# Battery_Monitoring_V2.net
KiCad netlist of a schematic drawn in EAGLE
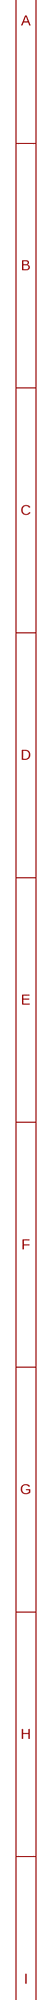
[diagram p0: schematic, sheet 1, part 1 of 2]
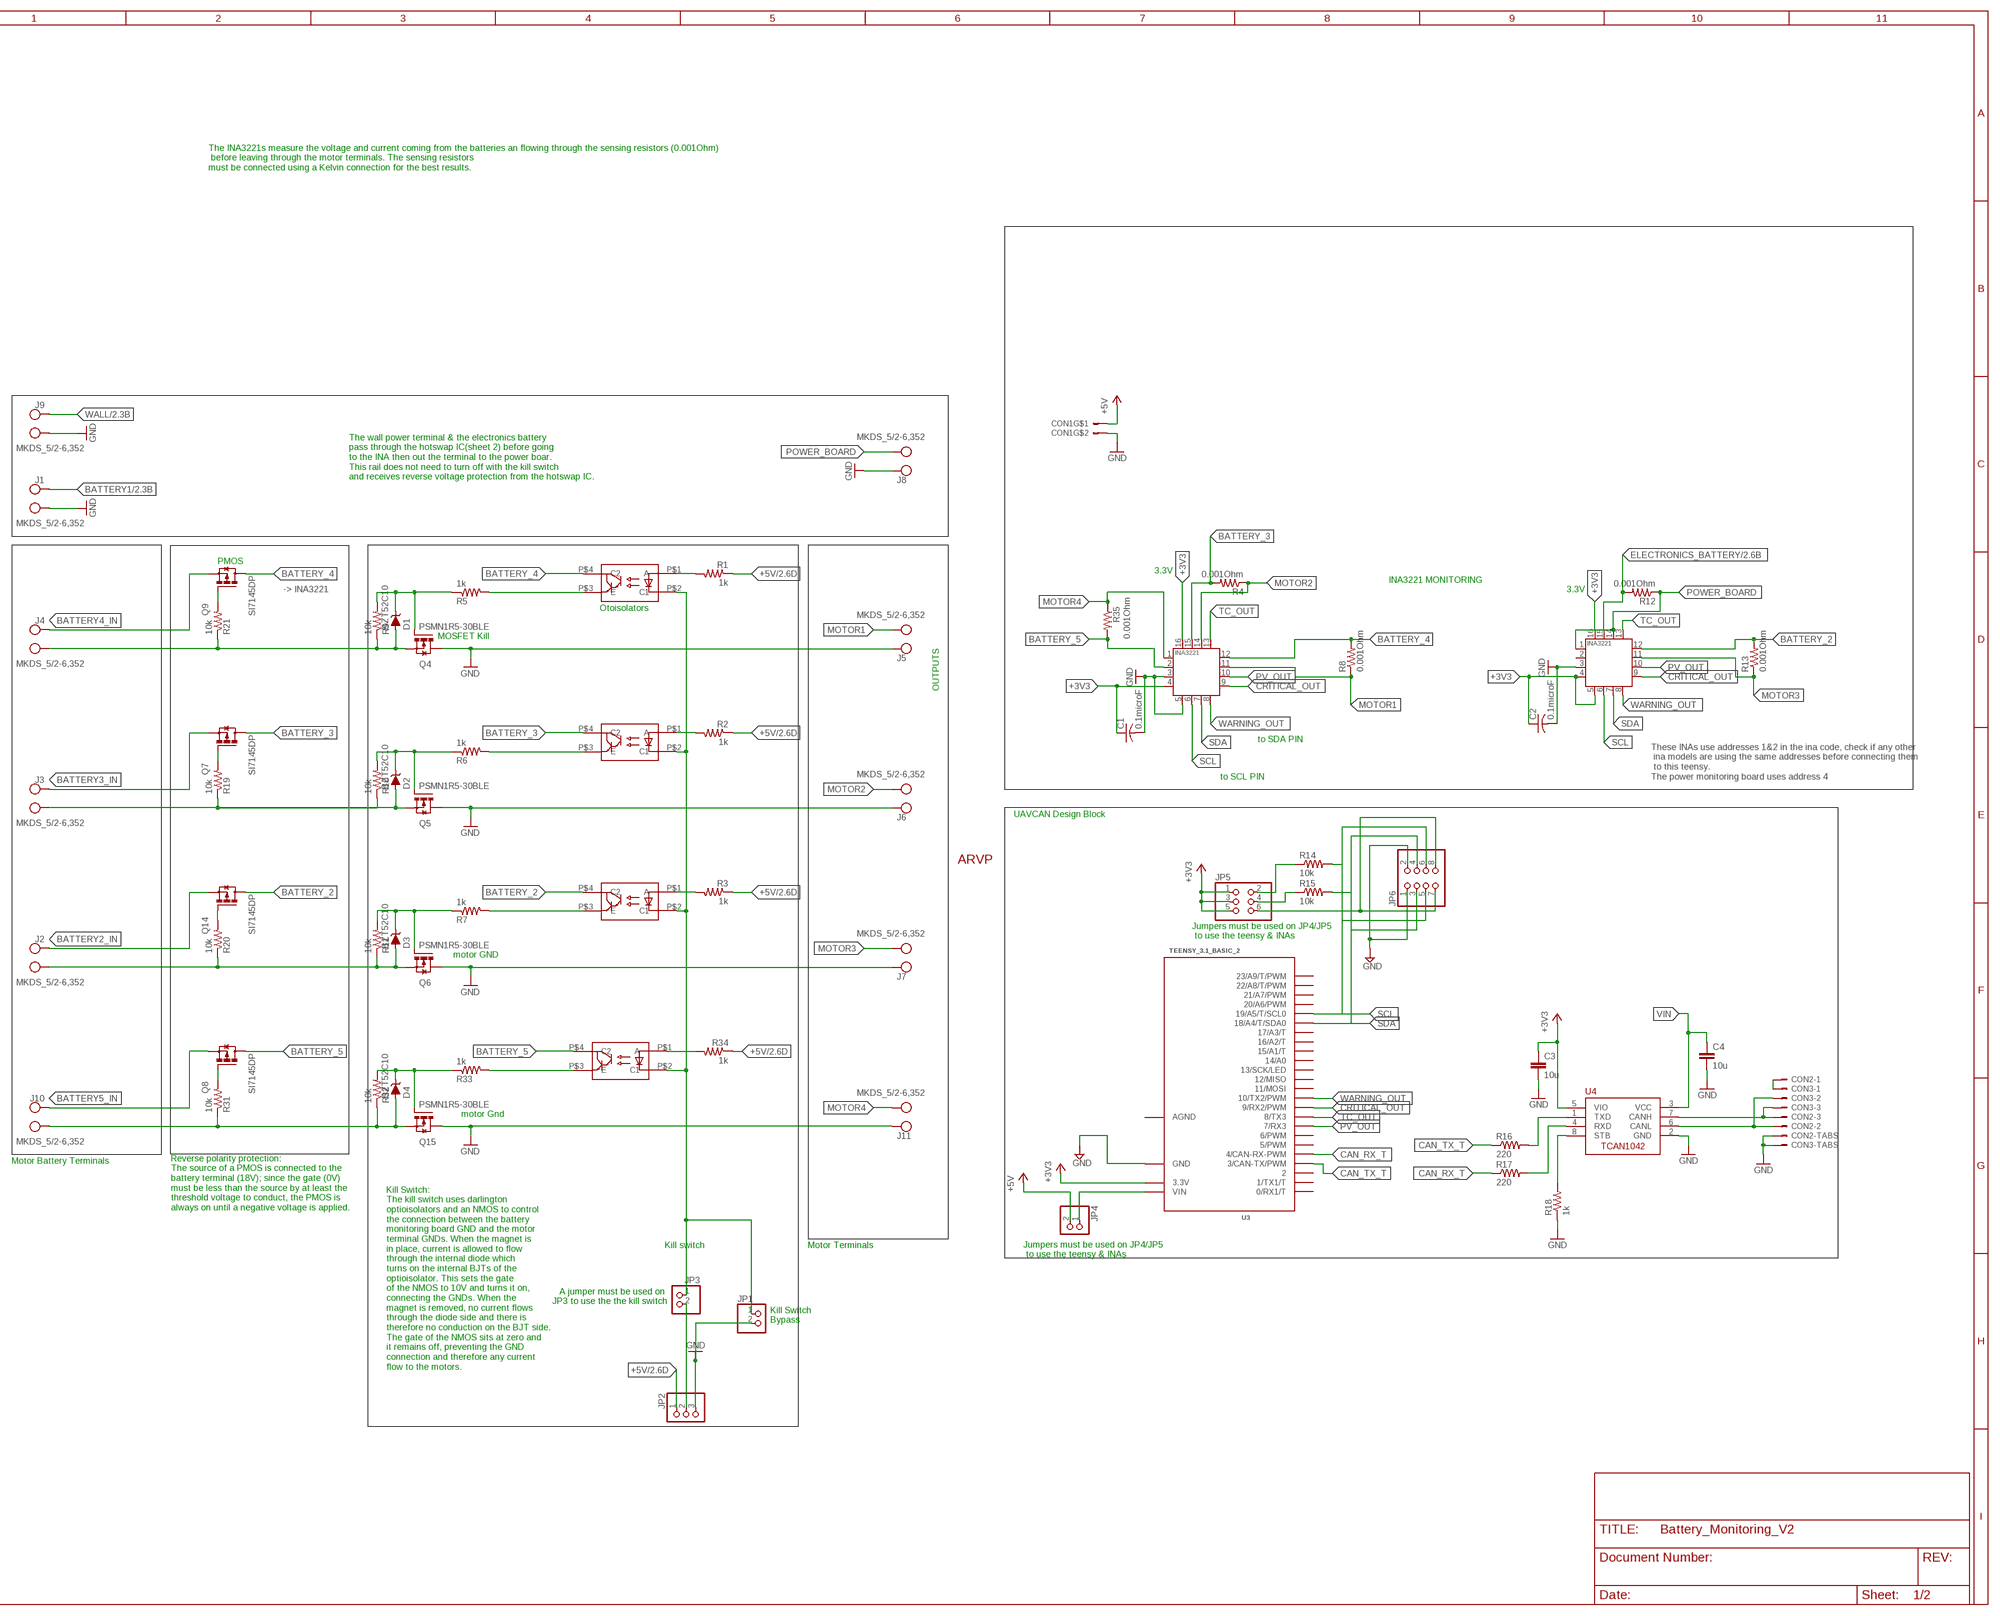
[diagram p1: schematic, sheet 1, part 2 of 2]
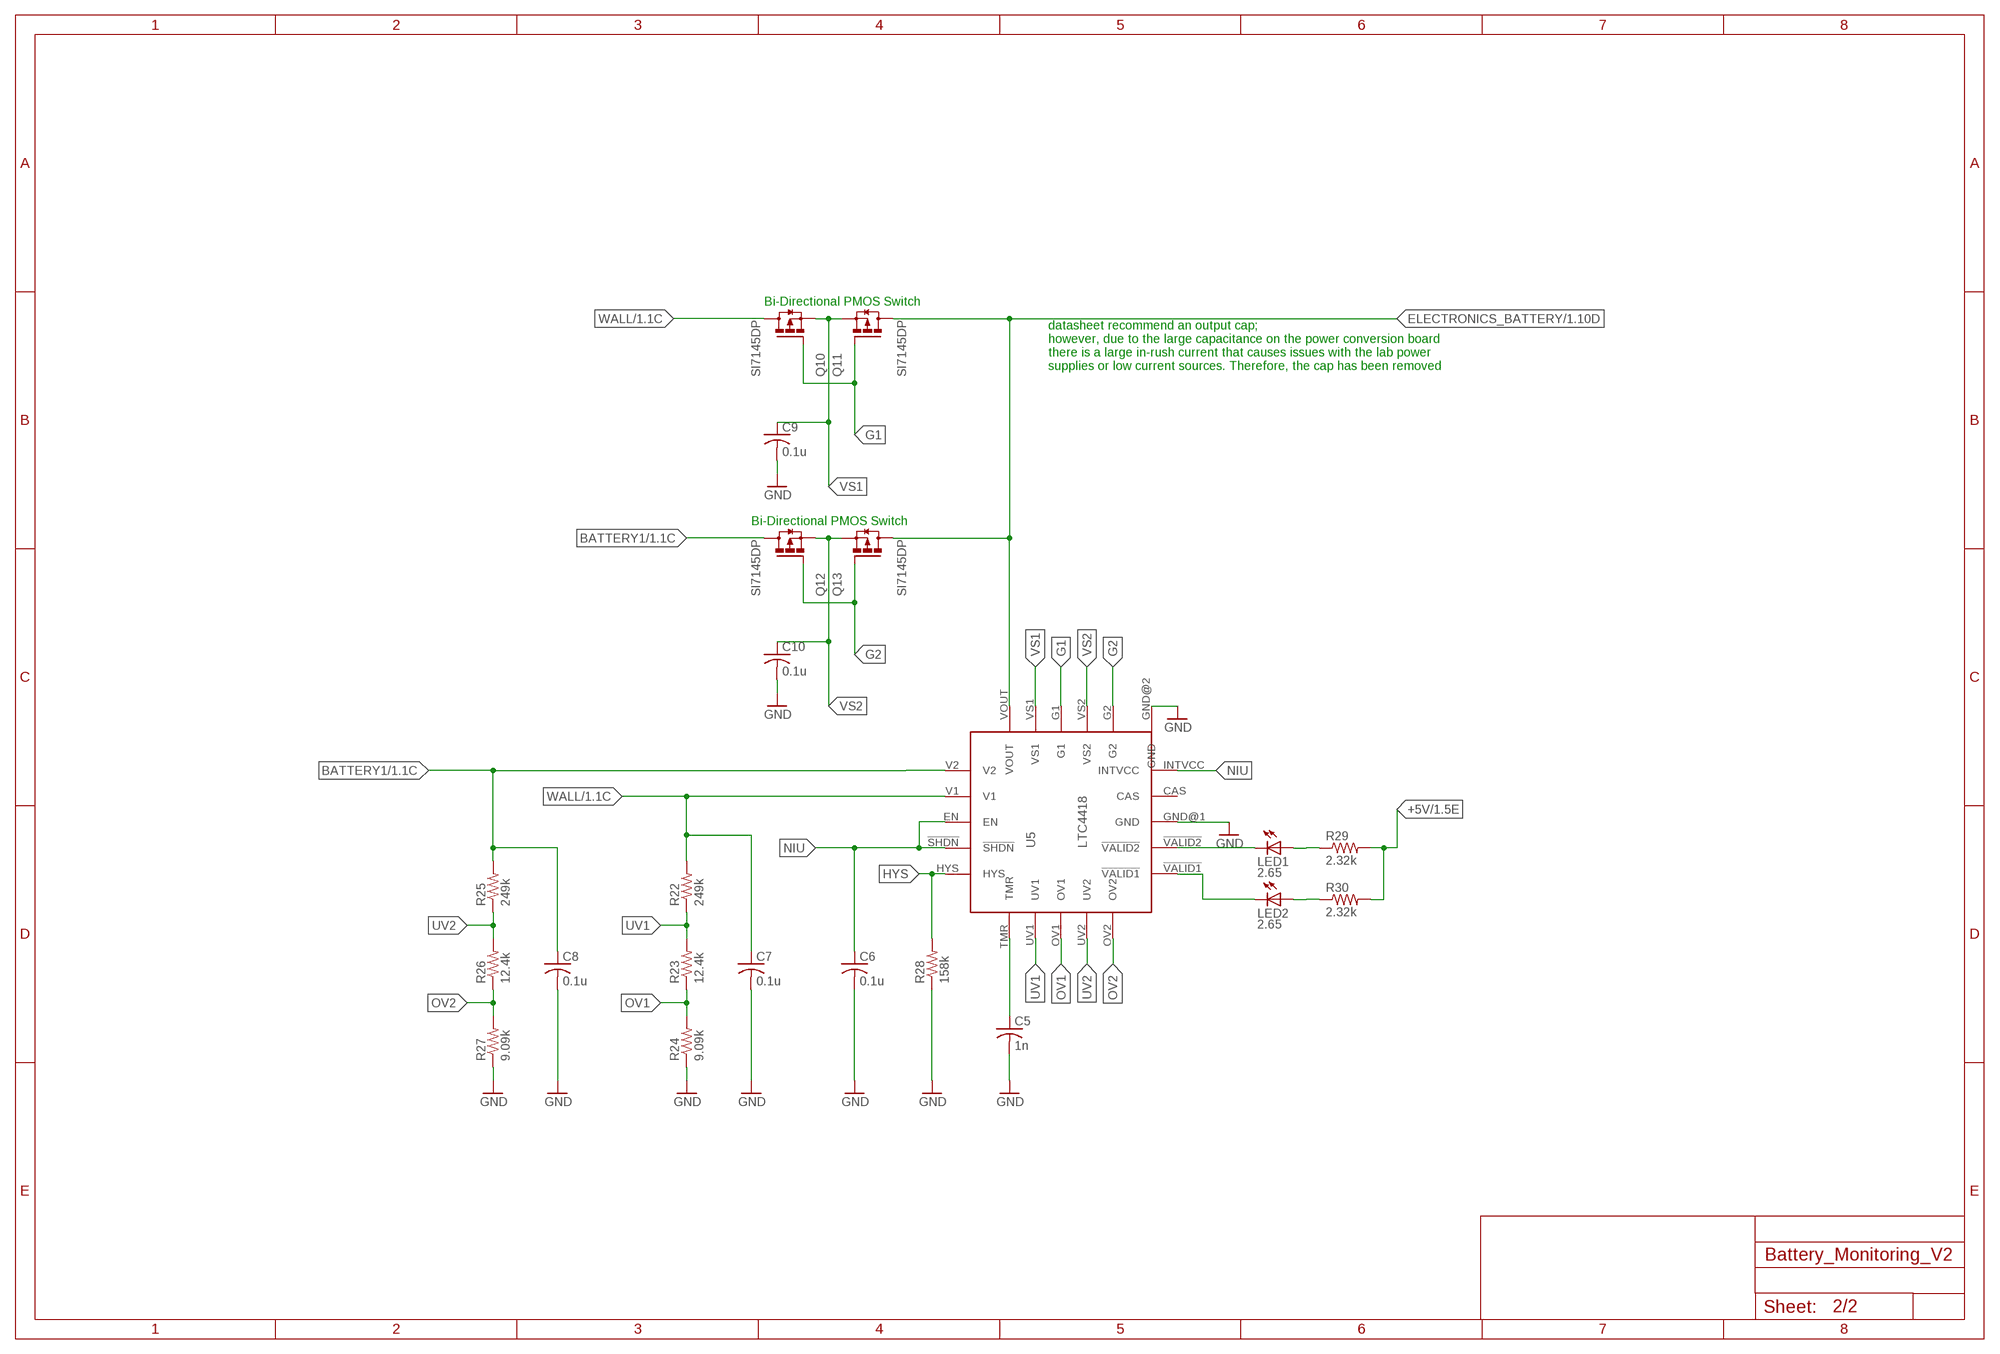
[diagram p2: schematic, sheet 2]

(export (version "E")
  (design (tool "Eeschema 10.0.6"))
  (components
    (comp (ref "ARVP1")
      (value "ARVP_LOGO")
      (footprint "eagle-import:ARVP")
      (libsource (lib "eagle-import") (part "ARVP_LOGO"))
    )
    (comp (ref "C1")
      (value "0.1microF")
      (footprint "eagle-import:C2012")
      (libsource (lib "eagle-import") (part "resistor_348_C-USC2012"))
    )
    (comp (ref "C2")
      (value "0.1microF")
      (footprint "eagle-import:C2012")
      (libsource (lib "eagle-import") (part "resistor_348_C-USC2012"))
    )
    (comp (ref "C3")
      (value "10u")
      (footprint "eagle-import:C0805")
      (libsource (lib "eagle-import") (part "C-EUC0805"))
    )
    (comp (ref "C4")
      (value "10u")
      (footprint "eagle-import:C0805")
      (libsource (lib "eagle-import") (part "C-EUC0805"))
    )
    (comp (ref "CON1")
      (value "MOLEX_5566-2")
      (footprint "eagle-import:5566-2")
      (libsource (lib "eagle-import") (part "MOLEX_5566-2"))
    )
    (comp (ref "CON2")
      (value "SM03B-GHS-TB")
      (footprint "eagle-import:SM03B-GHS-TB")
      (libsource (lib "eagle-import") (part "SM03B-GHS-TB"))
    )
    (comp (ref "CON3")
      (value "SM03B-GHS-TB")
      (footprint "eagle-import:SM03B-GHS-TB")
      (libsource (lib "eagle-import") (part "SM03B-GHS-TB"))
    )
    (comp (ref "D1")
      (value "BZT52C10")
      (footprint "eagle-import:SOD-123")
      (libsource (lib "eagle-import") (part "BZT52C10"))
    )
    (comp (ref "D2")
      (value "BZT52C10")
      (footprint "eagle-import:SOD-123")
      (libsource (lib "eagle-import") (part "BZT52C10"))
    )
    (comp (ref "D3")
      (value "BZT52C10")
      (footprint "eagle-import:SOD-123")
      (libsource (lib "eagle-import") (part "BZT52C10"))
    )
    (comp (ref "D4")
      (value "BZT52C10")
      (footprint "eagle-import:SOD-123")
      (libsource (lib "eagle-import") (part "BZT52C10"))
    )
    (comp (ref "J1")
      (value "MKDS_5/2-6,352")
      (footprint "eagle-import:MKDS_5_2-6,35")
      (libsource (lib "eagle-import") (part "MKDS_5/2-6,352"))
    )
    (comp (ref "J2")
      (value "MKDS_5/2-6,352")
      (footprint "eagle-import:MKDS_5_2-6,35")
      (libsource (lib "eagle-import") (part "MKDS_5/2-6,352"))
    )
    (comp (ref "J3")
      (value "MKDS_5/2-6,352")
      (footprint "eagle-import:MKDS_5_2-6,35")
      (libsource (lib "eagle-import") (part "MKDS_5/2-6,352"))
    )
    (comp (ref "J4")
      (value "MKDS_5/2-6,352")
      (footprint "eagle-import:MKDS_5_2-6,35")
      (libsource (lib "eagle-import") (part "MKDS_5/2-6,352"))
    )
    (comp (ref "J5")
      (value "MKDS_5/2-6,352")
      (footprint "eagle-import:MKDS_5_2-6,35")
      (libsource (lib "eagle-import") (part "MKDS_5/2-6,352"))
    )
    (comp (ref "J6")
      (value "MKDS_5/2-6,352")
      (footprint "eagle-import:MKDS_5_2-6,35")
      (libsource (lib "eagle-import") (part "MKDS_5/2-6,352"))
    )
    (comp (ref "J7")
      (value "MKDS_5/2-6,352")
      (footprint "eagle-import:MKDS_5_2-6,35")
      (libsource (lib "eagle-import") (part "MKDS_5/2-6,352"))
    )
    (comp (ref "J8")
      (value "MKDS_5/2-6,352")
      (footprint "eagle-import:MKDS_5_2-6,35")
      (libsource (lib "eagle-import") (part "MKDS_5/2-6,352"))
    )
    (comp (ref "J9")
      (value "MKDS_5/2-6,352")
      (footprint "eagle-import:MKDS_5_2-6,35")
      (libsource (lib "eagle-import") (part "MKDS_5/2-6,352"))
    )
    (comp (ref "J10")
      (value "MKDS_5/2-6,352")
      (footprint "eagle-import:MKDS_5_2-6,35")
      (libsource (lib "eagle-import") (part "MKDS_5/2-6,352"))
    )
    (comp (ref "J11")
      (value "MKDS_5/2-6,352")
      (footprint "eagle-import:MKDS_5_2-6,35")
      (libsource (lib "eagle-import") (part "MKDS_5/2-6,352"))
    )
    (comp (ref "JP1")
      (value "PINHD-1X2")
      (footprint "eagle-import:1X02")
      (libsource (lib "eagle-import") (part "PINHD-1X2"))
    )
    (comp (ref "JP2")
      (value "PINHD-1X3")
      (footprint "eagle-import:1X03")
      (libsource (lib "eagle-import") (part "PINHD-1X3"))
    )
    (comp (ref "JP3")
      (value "PINHD-1X2")
      (footprint "eagle-import:1X02")
      (libsource (lib "eagle-import") (part "PINHD-1X2"))
    )
    (comp (ref "JP4")
      (value "PINHD-1X2")
      (footprint "eagle-import:1X02")
      (libsource (lib "eagle-import") (part "PINHD-1X2"))
    )
    (comp (ref "JP5")
      (value "PINHD-2X3")
      (footprint "eagle-import:2X03")
      (libsource (lib "eagle-import") (part "PINHD-2X3"))
    )
    (comp (ref "JP6")
      (value "PINHD-2X4")
      (footprint "eagle-import:2X04")
      (libsource (lib "eagle-import") (part "PINHD-2X4"))
    )
    (comp (ref "Q1")
      (value "TCLD1000CT")
      (footprint "eagle-import:SOP-4L")
      (fields (field (name "SPICEPREFIX") "E"))
      (libsource (lib "eagle-import") (part "TCLD1000CT"))
    )
    (comp (ref "Q2")
      (value "TCLD1000CT")
      (footprint "eagle-import:SOP-4L")
      (libsource (lib "eagle-import") (part "TCLD1000CT"))
    )
    (comp (ref "Q3")
      (value "TCLD1000CT")
      (footprint "eagle-import:SOP-4L")
      (libsource (lib "eagle-import") (part "TCLD1000CT"))
    )
    (comp (ref "Q4")
      (value "PSMN1R5-30BLE")
      (footprint "eagle-import:SOT404_D2PAK")
      (libsource (lib "eagle-import") (part "PSMN1R5-30BLE"))
    )
    (comp (ref "Q5")
      (value "PSMN1R5-30BLE")
      (footprint "eagle-import:SOT404_D2PAK")
      (libsource (lib "eagle-import") (part "PSMN1R5-30BLE"))
    )
    (comp (ref "Q6")
      (value "PSMN1R5-30BLE")
      (footprint "eagle-import:SOT404_D2PAK")
      (libsource (lib "eagle-import") (part "PSMN1R5-30BLE"))
    )
    (comp (ref "Q7")
      (value "SI7145DP")
      (footprint "eagle-import:SO-8_PPAK_TEST")
      (fields (field (name "MPN") "SI7145DP-T1-GE3"))
      (libsource (lib "eagle-import") (part "Si7145DP_SI7145DP"))
    )
    (comp (ref "Q8")
      (value "SI7145DP")
      (footprint "eagle-import:SO-8_PPAK_TEST")
      (fields (field (name "MPN") "SI7145DP-T1-GE3"))
      (libsource (lib "eagle-import") (part "Si7145DP_SI7145DP"))
    )
    (comp (ref "Q9")
      (value "SI7145DP")
      (footprint "eagle-import:SO-8_PPAK_TEST")
      (fields (field (name "MPN") "SI7145DP-T1-GE3"))
      (libsource (lib "eagle-import") (part "Si7145DP_SI7145DP"))
    )
    (comp (ref "Q14")
      (value "SI7145DP")
      (footprint "eagle-import:SO-8_PPAK_TEST")
      (fields (field (name "MPN") "SI7145DP-T1-GE3"))
      (libsource (lib "eagle-import") (part "Si7145DP_SI7145DP"))
    )
    (comp (ref "Q15")
      (value "PSMN1R5-30BLE")
      (footprint "eagle-import:SOT404_D2PAK")
      (libsource (lib "eagle-import") (part "PSMN1R5-30BLE"))
    )
    (comp (ref "Q16")
      (value "TCLD1000CT")
      (footprint "eagle-import:SOP-4L")
      (libsource (lib "eagle-import") (part "TCLD1000CT"))
    )
    (comp (ref "R1")
      (value "1k")
      (footprint "eagle-import:R0805")
      (libsource (lib "eagle-import") (part "adafruit_420_R-US_R0805"))
    )
    (comp (ref "R2")
      (value "1k")
      (footprint "eagle-import:R0805")
      (libsource (lib "eagle-import") (part "adafruit_420_R-US_R0805"))
    )
    (comp (ref "R3")
      (value "1k")
      (footprint "eagle-import:R0805")
      (libsource (lib "eagle-import") (part "adafruit_420_R-US_R0805"))
    )
    (comp (ref "R4")
      (value "0.001Ohm")
      (footprint "eagle-import:3920")
      (libsource (lib "eagle-import") (part "HCS3920FT1L00"))
    )
    (comp (ref "R5")
      (value "1k")
      (footprint "eagle-import:M1206")
      (libsource (lib "eagle-import") (part "adafruit_420_R-US_M1206"))
    )
    (comp (ref "R6")
      (value "1k")
      (footprint "eagle-import:M1206")
      (libsource (lib "eagle-import") (part "adafruit_420_R-US_M1206"))
    )
    (comp (ref "R7")
      (value "1k")
      (footprint "eagle-import:M1206")
      (libsource (lib "eagle-import") (part "adafruit_420_R-US_M1206"))
    )
    (comp (ref "R8")
      (value "0.001Ohm")
      (footprint "eagle-import:3920")
      (libsource (lib "eagle-import") (part "HCS3920FT1L00"))
    )
    (comp (ref "R9")
      (value "10k")
      (footprint "eagle-import:M1206")
      (libsource (lib "eagle-import") (part "adafruit_420_R-US_M1206"))
    )
    (comp (ref "R10")
      (value "10k")
      (footprint "eagle-import:M1206")
      (libsource (lib "eagle-import") (part "adafruit_420_R-US_M1206"))
    )
    (comp (ref "R11")
      (value "10k")
      (footprint "eagle-import:M1206")
      (libsource (lib "eagle-import") (part "adafruit_420_R-US_M1206"))
    )
    (comp (ref "R12")
      (value "0.001Ohm")
      (footprint "eagle-import:3920")
      (libsource (lib "eagle-import") (part "HCS3920FT1L00"))
    )
    (comp (ref "R13")
      (value "0.001Ohm")
      (footprint "eagle-import:3920")
      (libsource (lib "eagle-import") (part "HCS3920FT1L00"))
    )
    (comp (ref "R14")
      (value "10k")
      (footprint "eagle-import:R1206")
      (libsource (lib "eagle-import") (part "rcl_334_R-US_R1206"))
    )
    (comp (ref "R15")
      (value "10k")
      (footprint "eagle-import:R1206")
      (libsource (lib "eagle-import") (part "rcl_334_R-US_R1206"))
    )
    (comp (ref "R16")
      (value "220")
      (footprint "eagle-import:R0805")
      (libsource (lib "eagle-import") (part "rcl_334_R-US_R0805"))
    )
    (comp (ref "R17")
      (value "220")
      (footprint "eagle-import:R0805")
      (libsource (lib "eagle-import") (part "rcl_334_R-US_R0805"))
    )
    (comp (ref "R18")
      (value "1k")
      (footprint "eagle-import:R0805")
      (libsource (lib "eagle-import") (part "rcl_334_R-US_R0805"))
    )
    (comp (ref "R19")
      (value "10k")
      (footprint "eagle-import:M1206")
      (fields (field (name "MPN") "RC0603FR-0710KL"))
      (libsource (lib "eagle-import") (part "R-US_M1206"))
    )
    (comp (ref "R20")
      (value "10k")
      (footprint "eagle-import:M1206")
      (fields (field (name "MPN") "RC0603FR-0710KL"))
      (libsource (lib "eagle-import") (part "R-US_M1206"))
    )
    (comp (ref "R21")
      (value "10k")
      (footprint "eagle-import:M1206")
      (fields (field (name "MPN") "RC0603FR-0710KL"))
      (libsource (lib "eagle-import") (part "adafruit_420_R-US_M1206"))
    )
    (comp (ref "R31")
      (value "10k")
      (footprint "eagle-import:M1206")
      (fields (field (name "MPN") "RC0603FR-0710KL"))
      (libsource (lib "eagle-import") (part "R-US_M1206"))
    )
    (comp (ref "R32")
      (value "10k")
      (footprint "eagle-import:M1206")
      (libsource (lib "eagle-import") (part "adafruit_420_R-US_M1206"))
    )
    (comp (ref "R33")
      (value "1k")
      (footprint "eagle-import:M1206")
      (libsource (lib "eagle-import") (part "adafruit_420_R-US_M1206"))
    )
    (comp (ref "R34")
      (value "1k")
      (footprint "eagle-import:R0805")
      (libsource (lib "eagle-import") (part "adafruit_420_R-US_R0805"))
    )
    (comp (ref "R35")
      (value "0.001Ohm")
      (footprint "eagle-import:3920")
      (libsource (lib "eagle-import") (part "HCS3920FT1L00"))
    )
    (comp (ref "U1")
      (value "INA3221.")
      (footprint "eagle-import:HVQFN16_4X4")
      (libsource (lib "eagle-import") (part "INA3221."))
    )
    (comp (ref "U2")
      (value "INA3221.")
      (footprint "eagle-import:HVQFN16_4X4")
      (libsource (lib "eagle-import") (part "INA3221."))
    )
    (comp (ref "U3")
      (value "TEENSY_3.1_BASIC_2")
      (footprint "eagle-import:TEENSY_3.1_BASIC_2")
      (libsource (lib "eagle-import") (part "TEENSY_3.1_BASIC_2"))
    )
    (comp (ref "U4")
      (value "TCAN1042HVDR")
      (footprint "eagle-import:SO-8")
      (libsource (lib "eagle-import") (part "TCAN1042HVDR"))
    )
    (comp (ref "C5")
      (value "1n")
      (footprint "eagle-import:C0805")
      (libsource (lib "eagle-import") (part "C-USC0805"))
    )
    (comp (ref "C6")
      (value "0.1u")
      (footprint "eagle-import:C0805")
      (libsource (lib "eagle-import") (part "C-USC0805"))
    )
    (comp (ref "C7")
      (value "0.1u")
      (footprint "eagle-import:C0805")
      (libsource (lib "eagle-import") (part "C-USC0805"))
    )
    (comp (ref "C8")
      (value "0.1u")
      (footprint "eagle-import:C0805")
      (libsource (lib "eagle-import") (part "C-USC0805"))
    )
    (comp (ref "C9")
      (value "0.1u")
      (footprint "eagle-import:C0805")
      (libsource (lib "eagle-import") (part "C-USC0805"))
    )
    (comp (ref "C10")
      (value "0.1u")
      (footprint "eagle-import:C0805")
      (libsource (lib "eagle-import") (part "C-USC0805"))
    )
    (comp (ref "LED1")
      (value "2.65")
      (footprint "eagle-import:SML0805")
      (libsource (lib "eagle-import") (part "LEDSML0805"))
    )
    (comp (ref "LED2")
      (value "2.65")
      (footprint "eagle-import:SML0805")
      (libsource (lib "eagle-import") (part "LEDSML0805"))
    )
    (comp (ref "Q10")
      (value "SI7145DP")
      (footprint "eagle-import:SO-8_PPAK_TEST")
      (libsource (lib "eagle-import") (part "SI7145DP"))
    )
    (comp (ref "Q11")
      (value "SI7145DP")
      (footprint "eagle-import:SO-8_PPAK_TEST")
      (libsource (lib "eagle-import") (part "SI7145DP"))
    )
    (comp (ref "Q12")
      (value "SI7145DP")
      (footprint "eagle-import:SO-8_PPAK_TEST")
      (libsource (lib "eagle-import") (part "SI7145DP"))
    )
    (comp (ref "Q13")
      (value "SI7145DP")
      (footprint "eagle-import:SO-8_PPAK_TEST")
      (libsource (lib "eagle-import") (part "SI7145DP"))
    )
    (comp (ref "R22")
      (value "249k")
      (footprint "eagle-import:R1206")
      (libsource (lib "eagle-import") (part "adafruit_420_R-US_R1206"))
    )
    (comp (ref "R23")
      (value "12.4k")
      (footprint "eagle-import:R0805")
      (libsource (lib "eagle-import") (part "adafruit_420_R-US_R0805"))
    )
    (comp (ref "R24")
      (value "9.09k")
      (footprint "eagle-import:R0805")
      (libsource (lib "eagle-import") (part "adafruit_420_R-US_R0805"))
    )
    (comp (ref "R25")
      (value "249k")
      (footprint "eagle-import:R1206")
      (libsource (lib "eagle-import") (part "adafruit_420_R-US_R1206"))
    )
    (comp (ref "R26")
      (value "12.4k")
      (footprint "eagle-import:R0805")
      (libsource (lib "eagle-import") (part "adafruit_420_R-US_R0805"))
    )
    (comp (ref "R27")
      (value "9.09k")
      (footprint "eagle-import:R0805")
      (libsource (lib "eagle-import") (part "adafruit_420_R-US_R0805"))
    )
    (comp (ref "R28")
      (value "158k")
      (footprint "eagle-import:R0805")
      (libsource (lib "eagle-import") (part "adafruit_420_R-US_R0805"))
    )
    (comp (ref "R29")
      (value "2.32k")
      (footprint "eagle-import:R0805")
      (libsource (lib "eagle-import") (part "adafruit_420_R-US_R0805"))
    )
    (comp (ref "R30")
      (value "2.32k")
      (footprint "eagle-import:R0805")
      (libsource (lib "eagle-import") (part "adafruit_420_R-US_R0805"))
    )
    (comp (ref "U5")
      (value "LTC4418")
      (footprint "eagle-import:20-QFN(4X4)")
      (libsource (lib "eagle-import") (part "LTC4418"))
    )
  )
  (nets
    (net (code "1") (name "+3V3") (class "Default")
      (node (ref "C1") (pin "1") (pinfunction "1_1") (pintype "passive"))
      (node (ref "C2") (pin "1") (pinfunction "1_1") (pintype "passive"))
      (node (ref "C3") (pin "1") (pinfunction "1_1") (pintype "passive"))
      (node (ref "JP5") (pin "1") (pinfunction "1_1") (pintype "passive"))
      (node (ref "JP5") (pin "3") (pinfunction "3_3") (pintype "passive"))
      (node (ref "JP5") (pin "5") (pinfunction "5_5") (pintype "passive"))
      (node (ref "U1") (pin "16") (pinfunction "VPU_16") (pintype "input"))
      (node (ref "U1") (pin "4") (pinfunction "VS_4") (pintype "power_in"))
      (node (ref "U2") (pin "16") (pinfunction "VPU_16") (pintype "input"))
      (node (ref "U2") (pin "4") (pinfunction "VS_4") (pintype "power_in"))
      (node (ref "U2") (pin "5") (pinfunction "A0_5") (pintype "input"))
      (node (ref "U3") (pin "3.3V") (pinfunction "3.3V_3.3V") (pintype "power_in"))
      (node (ref "U4") (pin "5") (pinfunction "VIO_5") (pintype "bidirectional"))
    )
    (net (code "2") (name "+5V") (class "Default")
      (node (ref "CON1") (pin "1") (pinfunction "S_1") (pintype "passive"))
      (node (ref "JP2") (pin "1") (pinfunction "1_1") (pintype "passive"))
      (node (ref "JP4") (pin "2") (pinfunction "2_2") (pintype "passive"))
      (node (ref "R1") (pin "1") (pinfunction "1_1") (pintype "passive"))
      (node (ref "R2") (pin "1") (pinfunction "1_1") (pintype "passive"))
      (node (ref "R29") (pin "2") (pinfunction "2_2") (pintype "passive"))
      (node (ref "R3") (pin "1") (pinfunction "1_1") (pintype "passive"))
      (node (ref "R30") (pin "2") (pinfunction "2_2") (pintype "passive"))
    )
    (net (code "3") (name "+5V{slash}2.6D") (class "Default")
      (node (ref "R34") (pin "1") (pinfunction "1_1") (pintype "passive"))
    )
    (net (code "4") (name "AGND") (class "Default")
      (node (ref "U3") (pin "AGND") (pinfunction "AGND_AGND") (pintype "power_in"))
    )
    (net (code "5") (name "BATTERY1") (class "Default")
      (node (ref "C8") (pin "1") (pinfunction "1_1") (pintype "passive"))
      (node (ref "J1") (pin "2") (pinfunction "KL1_2") (pintype "passive"))
      (node (ref "Q12") (pin "D@1") (pinfunction "D_D@1") (pintype "passive"))
      (node (ref "Q12") (pin "D@2") (pinfunction "D_D@2") (pintype "passive"))
      (node (ref "Q12") (pin "D@3") (pinfunction "D_D@3") (pintype "passive"))
      (node (ref "Q12") (pin "D@4") (pinfunction "D_D@4") (pintype "passive"))
      (node (ref "Q12") (pin "D@5") (pinfunction "D_D@5") (pintype "passive"))
      (node (ref "R25") (pin "2") (pinfunction "2_2") (pintype "passive"))
      (node (ref "U5") (pin "V2") (pinfunction "V2_V2") (pintype "bidirectional"))
    )
    (net (code "6") (name "BATTERY2_IN") (class "Default")
      (node (ref "J2") (pin "2") (pinfunction "KL1_2") (pintype "passive"))
      (node (ref "Q14") (pin "S@1") (pinfunction "S_S@1") (pintype "passive"))
      (node (ref "Q14") (pin "S@2") (pinfunction "S_S@2") (pintype "passive"))
      (node (ref "Q14") (pin "S@3") (pinfunction "S_S@3") (pintype "passive"))
    )
    (net (code "7") (name "BATTERY3_IN") (class "Default")
      (node (ref "J3") (pin "2") (pinfunction "KL1_2") (pintype "passive"))
      (node (ref "Q7") (pin "S@1") (pinfunction "S_S@1") (pintype "passive"))
      (node (ref "Q7") (pin "S@2") (pinfunction "S_S@2") (pintype "passive"))
      (node (ref "Q7") (pin "S@3") (pinfunction "S_S@3") (pintype "passive"))
    )
    (net (code "8") (name "BATTERY4_IN") (class "Default")
      (node (ref "J4") (pin "2") (pinfunction "KL1_2") (pintype "passive"))
      (node (ref "Q9") (pin "S@1") (pinfunction "S_S@1") (pintype "passive"))
      (node (ref "Q9") (pin "S@2") (pinfunction "S_S@2") (pintype "passive"))
      (node (ref "Q9") (pin "S@3") (pinfunction "S_S@3") (pintype "passive"))
    )
    (net (code "9") (name "BATTERY5_IN") (class "Default")
      (node (ref "J10") (pin "2") (pinfunction "KL1_2") (pintype "passive"))
      (node (ref "Q8") (pin "S@1") (pinfunction "S_S@1") (pintype "passive"))
      (node (ref "Q8") (pin "S@2") (pinfunction "S_S@2") (pintype "passive"))
      (node (ref "Q8") (pin "S@3") (pinfunction "S_S@3") (pintype "passive"))
    )
    (net (code "10") (name "BATTERY_2") (class "Default")
      (node (ref "Q14") (pin "D@1") (pinfunction "D_D@1") (pintype "passive"))
      (node (ref "Q14") (pin "D@2") (pinfunction "D_D@2") (pintype "passive"))
      (node (ref "Q14") (pin "D@3") (pinfunction "D_D@3") (pintype "passive"))
      (node (ref "Q14") (pin "D@4") (pinfunction "D_D@4") (pintype "passive"))
      (node (ref "Q14") (pin "D@5") (pinfunction "D_D@5") (pintype "passive"))
      (node (ref "Q3") (pin "P$4") (pinfunction "C2_P$4") (pintype "bidirectional"))
      (node (ref "R13") (pin "P$2") (pinfunction "2_P$2") (pintype "passive"))
      (node (ref "U2") (pin "12") (pinfunction "IN+1_12") (pintype "input"))
    )
    (net (code "11") (name "BATTERY_3") (class "Default")
      (node (ref "Q2") (pin "P$4") (pinfunction "C2_P$4") (pintype "bidirectional"))
      (node (ref "Q7") (pin "D@1") (pinfunction "D_D@1") (pintype "passive"))
      (node (ref "Q7") (pin "D@2") (pinfunction "D_D@2") (pintype "passive"))
      (node (ref "Q7") (pin "D@3") (pinfunction "D_D@3") (pintype "passive"))
      (node (ref "Q7") (pin "D@4") (pinfunction "D_D@4") (pintype "passive"))
      (node (ref "Q7") (pin "D@5") (pinfunction "D_D@5") (pintype "passive"))
      (node (ref "R4") (pin "P$2") (pinfunction "2_P$2") (pintype "passive"))
      (node (ref "U1") (pin "15") (pinfunction "IN+2_15") (pintype "input"))
    )
    (net (code "12") (name "BATTERY_4") (class "Default")
      (node (ref "Q1") (pin "P$4") (pinfunction "C2_P$4") (pintype "bidirectional"))
      (node (ref "Q9") (pin "D@1") (pinfunction "D_D@1") (pintype "passive"))
      (node (ref "Q9") (pin "D@2") (pinfunction "D_D@2") (pintype "passive"))
      (node (ref "Q9") (pin "D@3") (pinfunction "D_D@3") (pintype "passive"))
      (node (ref "Q9") (pin "D@4") (pinfunction "D_D@4") (pintype "passive"))
      (node (ref "Q9") (pin "D@5") (pinfunction "D_D@5") (pintype "passive"))
      (node (ref "R8") (pin "P$2") (pinfunction "2_P$2") (pintype "passive"))
      (node (ref "U1") (pin "12") (pinfunction "IN+1_12") (pintype "input"))
    )
    (net (code "13") (name "BATTERY_5") (class "Default")
      (node (ref "Q16") (pin "P$4") (pinfunction "C2_P$4") (pintype "bidirectional"))
      (node (ref "Q8") (pin "D@1") (pinfunction "D_D@1") (pintype "passive"))
      (node (ref "Q8") (pin "D@2") (pinfunction "D_D@2") (pintype "passive"))
      (node (ref "Q8") (pin "D@3") (pinfunction "D_D@3") (pintype "passive"))
      (node (ref "Q8") (pin "D@4") (pinfunction "D_D@4") (pintype "passive"))
      (node (ref "Q8") (pin "D@5") (pinfunction "D_D@5") (pintype "passive"))
      (node (ref "R35") (pin "P$2") (pinfunction "2_P$2") (pintype "passive"))
      (node (ref "U1") (pin "2") (pinfunction "IN+3_2") (pintype "input"))
    )
    (net (code "14") (name "CAN_RX_T") (class "Default")
      (node (ref "R17") (pin "1") (pinfunction "1_1") (pintype "passive"))
      (node (ref "U3") (pin "4") (pinfunction "4/CAN-RX-PWM_4") (pintype "bidirectional"))
    )
    (net (code "15") (name "CAN_TX_T") (class "Default")
      (node (ref "R16") (pin "1") (pinfunction "1_1") (pintype "passive"))
      (node (ref "U3") (pin "3") (pinfunction "3/CAN-TX/PWM_3") (pintype "bidirectional"))
    )
    (net (code "16") (name "CRITICAL_OUT") (class "Default")
      (node (ref "U1") (pin "9") (pinfunction "CRITICAL_9") (pintype "output"))
      (node (ref "U2") (pin "9") (pinfunction "CRITICAL_9") (pintype "output"))
      (node (ref "U3") (pin "9") (pinfunction "9/RX2/PWM_9") (pintype "bidirectional"))
    )
    (net (code "17") (name "ELECTRONICS_BATTERY") (class "Default")
      (node (ref "Q11") (pin "D@1") (pinfunction "D_D@1") (pintype "passive"))
      (node (ref "Q11") (pin "D@2") (pinfunction "D_D@2") (pintype "passive"))
      (node (ref "Q11") (pin "D@3") (pinfunction "D_D@3") (pintype "passive"))
      (node (ref "Q11") (pin "D@4") (pinfunction "D_D@4") (pintype "passive"))
      (node (ref "Q11") (pin "D@5") (pinfunction "D_D@5") (pintype "passive"))
      (node (ref "Q13") (pin "D@1") (pinfunction "D_D@1") (pintype "passive"))
      (node (ref "Q13") (pin "D@2") (pinfunction "D_D@2") (pintype "passive"))
      (node (ref "Q13") (pin "D@3") (pinfunction "D_D@3") (pintype "passive"))
      (node (ref "Q13") (pin "D@4") (pinfunction "D_D@4") (pintype "passive"))
      (node (ref "Q13") (pin "D@5") (pinfunction "D_D@5") (pintype "passive"))
      (node (ref "R12") (pin "P$2") (pinfunction "2_P$2") (pintype "passive"))
      (node (ref "U2") (pin "15") (pinfunction "IN+2_15") (pintype "input"))
      (node (ref "U5") (pin "VOUT") (pinfunction "VOUT_VOUT") (pintype "power_in"))
    )
    (net (code "18") (name "G1") (class "Default")
      (node (ref "Q10") (pin "G") (pinfunction "G_G") (pintype "passive"))
      (node (ref "Q11") (pin "G") (pinfunction "G_G") (pintype "passive"))
      (node (ref "U5") (pin "G1") (pinfunction "G1_G1") (pintype "bidirectional"))
    )
    (net (code "19") (name "G2") (class "Default")
      (node (ref "Q12") (pin "G") (pinfunction "G_G") (pintype "passive"))
      (node (ref "Q13") (pin "G") (pinfunction "G_G") (pintype "passive"))
      (node (ref "U5") (pin "G2") (pinfunction "G2_G2") (pintype "bidirectional"))
    )
    (net (code "20") (name "GND") (class "Default")
      (node (ref "C1") (pin "2") (pinfunction "2_2") (pintype "passive"))
      (node (ref "C10") (pin "2") (pinfunction "2_2") (pintype "passive"))
      (node (ref "C2") (pin "2") (pinfunction "2_2") (pintype "passive"))
      (node (ref "C3") (pin "2") (pinfunction "2_2") (pintype "passive"))
      (node (ref "C4") (pin "2") (pinfunction "2_2") (pintype "passive"))
      (node (ref "C5") (pin "2") (pinfunction "2_2") (pintype "passive"))
      (node (ref "C6") (pin "2") (pinfunction "2_2") (pintype "passive"))
      (node (ref "C7") (pin "2") (pinfunction "2_2") (pintype "passive"))
      (node (ref "C8") (pin "2") (pinfunction "2_2") (pintype "passive"))
      (node (ref "C9") (pin "2") (pinfunction "2_2") (pintype "passive"))
      (node (ref "CON1") (pin "2") (pinfunction "S_2") (pintype "passive"))
      (node (ref "CON2") (pin "P$4") (pinfunction "S_P$4") (pintype "passive"))
      (node (ref "CON2") (pin "P$5") (pinfunction "S_P$5") (pintype "passive"))
      (node (ref "CON3") (pin "P$4") (pinfunction "S_P$4") (pintype "passive"))
      (node (ref "CON3") (pin "P$5") (pinfunction "S_P$5") (pintype "passive"))
      (node (ref "J1") (pin "1") (pinfunction "KL_1") (pintype "passive"))
      (node (ref "J11") (pin "2") (pinfunction "KL1_2") (pintype "passive"))
      (node (ref "J5") (pin "2") (pinfunction "KL1_2") (pintype "passive"))
      (node (ref "J6") (pin "2") (pinfunction "KL1_2") (pintype "passive"))
      (node (ref "J7") (pin "2") (pinfunction "KL1_2") (pintype "passive"))
      (node (ref "J8") (pin "2") (pinfunction "KL1_2") (pintype "passive"))
      (node (ref "J9") (pin "1") (pinfunction "KL_1") (pintype "passive"))
      (node (ref "JP1") (pin "2") (pinfunction "2_2") (pintype "passive"))
      (node (ref "JP2") (pin "3") (pinfunction "3_3") (pintype "passive"))
      (node (ref "JP6") (pin "1") (pinfunction "1_1") (pintype "passive"))
      (node (ref "JP6") (pin "2") (pinfunction "2_2") (pintype "passive"))
      (node (ref "Q15") (pin "2D") (pinfunction "D_2D") (pintype "passive"))
      (node (ref "Q4") (pin "2D") (pinfunction "D_2D") (pintype "passive"))
      (node (ref "Q5") (pin "2D") (pinfunction "D_2D") (pintype "passive"))
      (node (ref "Q6") (pin "2D") (pinfunction "D_2D") (pintype "passive"))
      (node (ref "R18") (pin "1") (pinfunction "1_1") (pintype "passive"))
      (node (ref "R24") (pin "1") (pinfunction "1_1") (pintype "passive"))
      (node (ref "R27") (pin "1") (pinfunction "1_1") (pintype "passive"))
      (node (ref "R28") (pin "1") (pinfunction "1_1") (pintype "passive"))
      (node (ref "U1") (pin "3") (pinfunction "GND_3") (pintype "power_in"))
      (node (ref "U1") (pin "5") (pinfunction "A0_5") (pintype "input"))
      (node (ref "U2") (pin "3") (pinfunction "GND_3") (pintype "power_in"))
      (node (ref "U3") (pin "GND") (pinfunction "GND_GND") (pintype "power_in"))
      (node (ref "U4") (pin "2") (pinfunction "GND_2") (pintype "bidirectional"))
      (node (ref "U5") (pin "GND@1") (pinfunction "GND_GND@1") (pintype "power_in"))
      (node (ref "U5") (pin "GND@2") (pinfunction "GND_GND@2") (pintype "power_in"))
    )
    (net (code "21") (name "HYS") (class "Default")
      (node (ref "R28") (pin "2") (pinfunction "2_2") (pintype "passive"))
      (node (ref "U5") (pin "HYS") (pinfunction "HYS_HYS") (pintype "bidirectional"))
    )
    (net (code "22") (name "MOTOR1") (class "Default")
      (node (ref "J5") (pin "1") (pinfunction "KL_1") (pintype "passive"))
      (node (ref "R8") (pin "P$1") (pinfunction "1_P$1") (pintype "passive"))
      (node (ref "U1") (pin "11") (pinfunction "IN-1_11") (pintype "input"))
    )
    (net (code "23") (name "MOTOR2") (class "Default")
      (node (ref "J6") (pin "1") (pinfunction "KL_1") (pintype "passive"))
      (node (ref "R4") (pin "P$1") (pinfunction "1_P$1") (pintype "passive"))
      (node (ref "U1") (pin "14") (pinfunction "IN-2_14") (pintype "input"))
    )
    (net (code "24") (name "MOTOR3") (class "Default")
      (node (ref "J7") (pin "1") (pinfunction "KL_1") (pintype "passive"))
      (node (ref "R13") (pin "P$1") (pinfunction "1_P$1") (pintype "passive"))
      (node (ref "U2") (pin "11") (pinfunction "IN-1_11") (pintype "input"))
    )
    (net (code "25") (name "MOTOR4") (class "Default")
      (node (ref "J11") (pin "1") (pinfunction "KL_1") (pintype "passive"))
      (node (ref "R35") (pin "P$1") (pinfunction "1_P$1") (pintype "passive"))
      (node (ref "U1") (pin "1") (pinfunction "IN-3_1") (pintype "input"))
    )
    (net (code "26") (name "NIU") (class "Default")
      (node (ref "C6") (pin "1") (pinfunction "1_1") (pintype "passive"))
      (node (ref "U5") (pin "!SHDN") (pinfunction "~{SHDN}_!SHDN") (pintype "bidirectional"))
      (node (ref "U5") (pin "EN") (pinfunction "EN_EN") (pintype "bidirectional"))
      (node (ref "U5") (pin "INTVCC") (pinfunction "INTVCC_INTVCC") (pintype "bidirectional"))
    )
    (net (code "27") (name "Net-(C5-Pad1)") (class "Default")
      (node (ref "C5") (pin "1") (pinfunction "1_1") (pintype "passive"))
      (node (ref "U5") (pin "TMR") (pinfunction "TMR_TMR") (pintype "bidirectional"))
    )
    (net (code "28") (name "Net-(CON2A-S)") (class "Default")
      (node (ref "CON2") (pin "P$1") (pinfunction "S_P$1") (pintype "passive"))
      (node (ref "CON3") (pin "P$1") (pinfunction "S_P$1") (pintype "passive"))
    )
    (net (code "29") (name "Net-(CON2B-S)") (class "Default")
      (node (ref "CON2") (pin "P$2") (pinfunction "S_P$2") (pintype "passive"))
      (node (ref "CON3") (pin "P$2") (pinfunction "S_P$2") (pintype "passive"))
      (node (ref "U4") (pin "6") (pinfunction "CANL_6") (pintype "bidirectional"))
    )
    (net (code "30") (name "Net-(CON2C-S)") (class "Default")
      (node (ref "CON2") (pin "P$3") (pinfunction "S_P$3") (pintype "passive"))
      (node (ref "CON3") (pin "P$3") (pinfunction "S_P$3") (pintype "passive"))
      (node (ref "U4") (pin "7") (pinfunction "CANH_7") (pintype "bidirectional"))
    )
    (net (code "31") (name "Net-(D1-A)") (class "Default")
      (node (ref "D1") (pin "P$2") (pinfunction "A_P$2") (pintype "passive"))
      (node (ref "J4") (pin "1") (pinfunction "KL_1") (pintype "passive"))
      (node (ref "Q4") (pin "3S") (pinfunction "S_3S") (pintype "passive"))
      (node (ref "R21") (pin "1") (pinfunction "1_1") (pintype "passive"))
      (node (ref "R9") (pin "1") (pinfunction "1_1") (pintype "passive"))
    )
    (net (code "32") (name "Net-(D1-C)") (class "Default")
      (node (ref "D1") (pin "P$1") (pinfunction "C_P$1") (pintype "passive"))
      (node (ref "Q4") (pin "1G") (pinfunction "G_1G") (pintype "passive"))
      (node (ref "R5") (pin "1") (pinfunction "1_1") (pintype "passive"))
      (node (ref "R9") (pin "2") (pinfunction "2_2") (pintype "passive"))
    )
    (net (code "33") (name "Net-(D2-A)") (class "Default")
      (node (ref "D2") (pin "P$2") (pinfunction "A_P$2") (pintype "passive"))
      (node (ref "J3") (pin "1") (pinfunction "KL_1") (pintype "passive"))
      (node (ref "Q5") (pin "3S") (pinfunction "S_3S") (pintype "passive"))
      (node (ref "R10") (pin "1") (pinfunction "1_1") (pintype "passive"))
      (node (ref "R19") (pin "1") (pinfunction "1_1") (pintype "passive"))
    )
    (net (code "34") (name "Net-(D2-C)") (class "Default")
      (node (ref "D2") (pin "P$1") (pinfunction "C_P$1") (pintype "passive"))
      (node (ref "Q5") (pin "1G") (pinfunction "G_1G") (pintype "passive"))
      (node (ref "R10") (pin "2") (pinfunction "2_2") (pintype "passive"))
      (node (ref "R6") (pin "1") (pinfunction "1_1") (pintype "passive"))
    )
    (net (code "35") (name "Net-(D3-A)") (class "Default")
      (node (ref "D3") (pin "P$2") (pinfunction "A_P$2") (pintype "passive"))
      (node (ref "J2") (pin "1") (pinfunction "KL_1") (pintype "passive"))
      (node (ref "Q6") (pin "3S") (pinfunction "S_3S") (pintype "passive"))
      (node (ref "R11") (pin "1") (pinfunction "1_1") (pintype "passive"))
      (node (ref "R20") (pin "1") (pinfunction "1_1") (pintype "passive"))
    )
    (net (code "36") (name "Net-(D3-C)") (class "Default")
      (node (ref "D3") (pin "P$1") (pinfunction "C_P$1") (pintype "passive"))
      (node (ref "Q6") (pin "1G") (pinfunction "G_1G") (pintype "passive"))
      (node (ref "R11") (pin "2") (pinfunction "2_2") (pintype "passive"))
      (node (ref "R7") (pin "1") (pinfunction "1_1") (pintype "passive"))
    )
    (net (code "37") (name "Net-(D4-A)") (class "Default")
      (node (ref "D4") (pin "P$2") (pinfunction "A_P$2") (pintype "passive"))
      (node (ref "J10") (pin "1") (pinfunction "KL_1") (pintype "passive"))
      (node (ref "Q15") (pin "3S") (pinfunction "S_3S") (pintype "passive"))
      (node (ref "R31") (pin "1") (pinfunction "1_1") (pintype "passive"))
      (node (ref "R32") (pin "1") (pinfunction "1_1") (pintype "passive"))
    )
    (net (code "38") (name "Net-(D4-C)") (class "Default")
      (node (ref "D4") (pin "P$1") (pinfunction "C_P$1") (pintype "passive"))
      (node (ref "Q15") (pin "1G") (pinfunction "G_1G") (pintype "passive"))
      (node (ref "R32") (pin "2") (pinfunction "2_2") (pintype "passive"))
      (node (ref "R33") (pin "1") (pinfunction "1_1") (pintype "passive"))
    )
    (net (code "39") (name "Net-(JP2-Pad2)") (class "Default")
      (node (ref "JP2") (pin "2") (pinfunction "2_2") (pintype "passive"))
      (node (ref "JP3") (pin "2") (pinfunction "2_2") (pintype "passive"))
    )
    (net (code "40") (name "Net-(JP5-Pad2)") (class "Default")
      (node (ref "JP5") (pin "2") (pinfunction "2_2") (pintype "passive"))
      (node (ref "R14") (pin "1") (pinfunction "1_1") (pintype "passive"))
    )
    (net (code "41") (name "Net-(JP5-Pad4)") (class "Default")
      (node (ref "JP5") (pin "4") (pinfunction "4_4") (pintype "passive"))
      (node (ref "R15") (pin "1") (pinfunction "1_1") (pintype "passive"))
    )
    (net (code "42") (name "Net-(JP5-Pad6)") (class "Default")
      (node (ref "JP5") (pin "6") (pinfunction "6_6") (pintype "passive"))
      (node (ref "JP6") (pin "7") (pinfunction "7_7") (pintype "passive"))
      (node (ref "JP6") (pin "8") (pinfunction "8_8") (pintype "passive"))
    )
    (net (code "43") (name "Net-(LED1-PadA)") (class "Default")
      (node (ref "LED1") (pin "A") (pinfunction "A_A") (pintype "passive"))
      (node (ref "R29") (pin "1") (pinfunction "1_1") (pintype "passive"))
    )
    (net (code "44") (name "Net-(LED2-PadA)") (class "Default")
      (node (ref "LED2") (pin "A") (pinfunction "A_A") (pintype "passive"))
      (node (ref "R30") (pin "1") (pinfunction "1_1") (pintype "passive"))
    )
    (net (code "45") (name "Net-(Q1-A)") (class "Default")
      (node (ref "Q1") (pin "P$1") (pinfunction "A_P$1") (pintype "bidirectional"))
      (node (ref "R1") (pin "2") (pinfunction "2_2") (pintype "passive"))
    )
    (net (code "46") (name "Net-(Q1-C1)") (class "Default")
      (node (ref "JP1") (pin "1") (pinfunction "1_1") (pintype "passive"))
      (node (ref "JP3") (pin "1") (pinfunction "1_1") (pintype "passive"))
      (node (ref "Q1") (pin "P$2") (pinfunction "C1_P$2") (pintype "bidirectional"))
      (node (ref "Q16") (pin "P$2") (pinfunction "C1_P$2") (pintype "bidirectional"))
      (node (ref "Q2") (pin "P$2") (pinfunction "C1_P$2") (pintype "bidirectional"))
      (node (ref "Q3") (pin "P$2") (pinfunction "C1_P$2") (pintype "bidirectional"))
    )
    (net (code "47") (name "Net-(Q1-E)") (class "Default")
      (node (ref "Q1") (pin "P$3") (pinfunction "E_P$3") (pintype "bidirectional"))
      (node (ref "R5") (pin "2") (pinfunction "2_2") (pintype "passive"))
    )
    (net (code "48") (name "Net-(Q2-A)") (class "Default")
      (node (ref "Q2") (pin "P$1") (pinfunction "A_P$1") (pintype "bidirectional"))
      (node (ref "R2") (pin "2") (pinfunction "2_2") (pintype "passive"))
    )
    (net (code "49") (name "Net-(Q2-E)") (class "Default")
      (node (ref "Q2") (pin "P$3") (pinfunction "E_P$3") (pintype "bidirectional"))
      (node (ref "R6") (pin "2") (pinfunction "2_2") (pintype "passive"))
    )
    (net (code "50") (name "Net-(Q3-A)") (class "Default")
      (node (ref "Q3") (pin "P$1") (pinfunction "A_P$1") (pintype "bidirectional"))
      (node (ref "R3") (pin "2") (pinfunction "2_2") (pintype "passive"))
    )
    (net (code "51") (name "Net-(Q3-E)") (class "Default")
      (node (ref "Q3") (pin "P$3") (pinfunction "E_P$3") (pintype "bidirectional"))
      (node (ref "R7") (pin "2") (pinfunction "2_2") (pintype "passive"))
    )
    (net (code "52") (name "Net-(Q7-PadG)") (class "Default")
      (node (ref "Q7") (pin "G") (pinfunction "G_G") (pintype "passive"))
      (node (ref "R19") (pin "2") (pinfunction "2_2") (pintype "passive"))
    )
    (net (code "53") (name "Net-(Q8-PadG)") (class "Default")
      (node (ref "Q8") (pin "G") (pinfunction "G_G") (pintype "passive"))
      (node (ref "R31") (pin "2") (pinfunction "2_2") (pintype "passive"))
    )
    (net (code "54") (name "Net-(Q9-PadG)") (class "Default")
      (node (ref "Q9") (pin "G") (pinfunction "G_G") (pintype "passive"))
      (node (ref "R21") (pin "2") (pinfunction "2_2") (pintype "passive"))
    )
    (net (code "55") (name "Net-(Q14-PadG)") (class "Default")
      (node (ref "Q14") (pin "G") (pinfunction "G_G") (pintype "passive"))
      (node (ref "R20") (pin "2") (pinfunction "2_2") (pintype "passive"))
    )
    (net (code "56") (name "Net-(Q16-A)") (class "Default")
      (node (ref "Q16") (pin "P$1") (pinfunction "A_P$1") (pintype "bidirectional"))
      (node (ref "R34") (pin "2") (pinfunction "2_2") (pintype "passive"))
    )
    (net (code "57") (name "Net-(Q16-E)") (class "Default")
      (node (ref "Q16") (pin "P$3") (pinfunction "E_P$3") (pintype "bidirectional"))
      (node (ref "R33") (pin "2") (pinfunction "2_2") (pintype "passive"))
    )
    (net (code "58") (name "Net-(U4-RXD)") (class "Default")
      (node (ref "R17") (pin "2") (pinfunction "2_2") (pintype "passive"))
      (node (ref "U4") (pin "4") (pinfunction "RXD_4") (pintype "bidirectional"))
    )
    (net (code "59") (name "Net-(U4-STB)") (class "Default")
      (node (ref "R18") (pin "2") (pinfunction "2_2") (pintype "passive"))
      (node (ref "U4") (pin "8") (pinfunction "STB_8") (pintype "bidirectional"))
    )
    (net (code "60") (name "Net-(U4-TXD)") (class "Default")
      (node (ref "R16") (pin "2") (pinfunction "2_2") (pintype "passive"))
      (node (ref "U4") (pin "1") (pinfunction "TXD_1") (pintype "bidirectional"))
    )
    (net (code "61") (name "Net-(U5-~{VALID1})") (class "Default")
      (node (ref "LED2") (pin "C") (pinfunction "C_C") (pintype "passive"))
      (node (ref "U5") (pin "!VALID1") (pinfunction "~{VALID1}_!VALID1") (pintype "bidirectional"))
    )
    (net (code "62") (name "Net-(U5-~{VALID2})") (class "Default")
      (node (ref "LED1") (pin "C") (pinfunction "C_C") (pintype "passive"))
      (node (ref "U5") (pin "!VALID2") (pinfunction "~{VALID2}_!VALID2") (pintype "bidirectional"))
    )
    (net (code "63") (name "OV1") (class "Default")
      (node (ref "R23") (pin "1") (pinfunction "1_1") (pintype "passive"))
      (node (ref "R24") (pin "2") (pinfunction "2_2") (pintype "passive"))
      (node (ref "U5") (pin "OV1") (pinfunction "OV1_OV1") (pintype "bidirectional"))
    )
    (net (code "64") (name "OV2") (class "Default")
      (node (ref "R26") (pin "1") (pinfunction "1_1") (pintype "passive"))
      (node (ref "R27") (pin "2") (pinfunction "2_2") (pintype "passive"))
      (node (ref "U5") (pin "OV2") (pinfunction "OV2_OV2") (pintype "bidirectional"))
    )
    (net (code "65") (name "POWER_BOARD") (class "Default")
      (node (ref "J8") (pin "1") (pinfunction "KL_1") (pintype "passive"))
      (node (ref "R12") (pin "P$1") (pinfunction "1_P$1") (pintype "passive"))
      (node (ref "U2") (pin "1") (pinfunction "IN-3_1") (pintype "input"))
      (node (ref "U2") (pin "14") (pinfunction "IN-2_14") (pintype "input"))
    )
    (net (code "66") (name "PV_OUT") (class "Default")
      (node (ref "U1") (pin "10") (pinfunction "PV_10") (pintype "output"))
      (node (ref "U2") (pin "10") (pinfunction "PV_10") (pintype "output"))
      (node (ref "U3") (pin "7") (pinfunction "7/RX3_7") (pintype "bidirectional"))
    )
    (net (code "67") (name "SCL") (class "Default")
      (node (ref "JP6") (pin "5") (pinfunction "5_5") (pintype "passive"))
      (node (ref "JP6") (pin "6") (pinfunction "6_6") (pintype "passive"))
      (node (ref "R14") (pin "2") (pinfunction "2_2") (pintype "passive"))
      (node (ref "U1") (pin "6") (pinfunction "SCL_6") (pintype "input"))
      (node (ref "U2") (pin "6") (pinfunction "SCL_6") (pintype "input"))
      (node (ref "U3") (pin "19/A5") (pinfunction "19/A5/T/SCL0_19/A5") (pintype "bidirectional"))
    )
    (net (code "68") (name "SDA") (class "Default")
      (node (ref "JP6") (pin "3") (pinfunction "3_3") (pintype "passive"))
      (node (ref "JP6") (pin "4") (pinfunction "4_4") (pintype "passive"))
      (node (ref "R15") (pin "2") (pinfunction "2_2") (pintype "passive"))
      (node (ref "U1") (pin "7") (pinfunction "SDA_7") (pintype "bidirectional"))
      (node (ref "U2") (pin "7") (pinfunction "SDA_7") (pintype "bidirectional"))
      (node (ref "U3") (pin "18/A4") (pinfunction "18/A4/T/SDA0_18/A4") (pintype "bidirectional"))
    )
    (net (code "69") (name "TC_OUT") (class "Default")
      (node (ref "U1") (pin "13") (pinfunction "TC_13") (pintype "output"))
      (node (ref "U2") (pin "13") (pinfunction "TC_13") (pintype "output"))
      (node (ref "U3") (pin "8") (pinfunction "8/TX3_8") (pintype "bidirectional"))
    )
    (net (code "70") (name "UV1") (class "Default")
      (node (ref "R22") (pin "1") (pinfunction "1_1") (pintype "passive"))
      (node (ref "R23") (pin "2") (pinfunction "2_2") (pintype "passive"))
      (node (ref "U5") (pin "UV1") (pinfunction "UV1_UV1") (pintype "bidirectional"))
    )
    (net (code "71") (name "UV2") (class "Default")
      (node (ref "R25") (pin "1") (pinfunction "1_1") (pintype "passive"))
      (node (ref "R26") (pin "2") (pinfunction "2_2") (pintype "passive"))
      (node (ref "U5") (pin "UV2") (pinfunction "UV2_UV2") (pintype "bidirectional"))
    )
    (net (code "72") (name "VIN") (class "Default")
      (node (ref "C4") (pin "1") (pinfunction "1_1") (pintype "passive"))
      (node (ref "JP4") (pin "1") (pinfunction "1_1") (pintype "passive"))
      (node (ref "U3") (pin "VIN") (pinfunction "VIN_VIN") (pintype "power_in"))
      (node (ref "U4") (pin "3") (pinfunction "VCC_3") (pintype "bidirectional"))
    )
    (net (code "73") (name "VS1") (class "Default")
      (node (ref "C9") (pin "1") (pinfunction "1_1") (pintype "passive"))
      (node (ref "Q10") (pin "S@1") (pinfunction "S_S@1") (pintype "passive"))
      (node (ref "Q10") (pin "S@2") (pinfunction "S_S@2") (pintype "passive"))
      (node (ref "Q10") (pin "S@3") (pinfunction "S_S@3") (pintype "passive"))
      (node (ref "Q11") (pin "S@1") (pinfunction "S_S@1") (pintype "passive"))
      (node (ref "Q11") (pin "S@2") (pinfunction "S_S@2") (pintype "passive"))
      (node (ref "Q11") (pin "S@3") (pinfunction "S_S@3") (pintype "passive"))
      (node (ref "U5") (pin "VS1") (pinfunction "VS1_VS1") (pintype "bidirectional"))
    )
    (net (code "74") (name "VS2") (class "Default")
      (node (ref "C10") (pin "1") (pinfunction "1_1") (pintype "passive"))
      (node (ref "Q12") (pin "S@1") (pinfunction "S_S@1") (pintype "passive"))
      (node (ref "Q12") (pin "S@2") (pinfunction "S_S@2") (pintype "passive"))
      (node (ref "Q12") (pin "S@3") (pinfunction "S_S@3") (pintype "passive"))
      (node (ref "Q13") (pin "S@1") (pinfunction "S_S@1") (pintype "passive"))
      (node (ref "Q13") (pin "S@2") (pinfunction "S_S@2") (pintype "passive"))
      (node (ref "Q13") (pin "S@3") (pinfunction "S_S@3") (pintype "passive"))
      (node (ref "U5") (pin "VS2") (pinfunction "VS2_VS2") (pintype "bidirectional"))
    )
    (net (code "75") (name "WALL") (class "Default")
      (node (ref "C7") (pin "1") (pinfunction "1_1") (pintype "passive"))
      (node (ref "J9") (pin "2") (pinfunction "KL1_2") (pintype "passive"))
      (node (ref "Q10") (pin "D@1") (pinfunction "D_D@1") (pintype "passive"))
      (node (ref "Q10") (pin "D@2") (pinfunction "D_D@2") (pintype "passive"))
      (node (ref "Q10") (pin "D@3") (pinfunction "D_D@3") (pintype "passive"))
      (node (ref "Q10") (pin "D@4") (pinfunction "D_D@4") (pintype "passive"))
      (node (ref "Q10") (pin "D@5") (pinfunction "D_D@5") (pintype "passive"))
      (node (ref "R22") (pin "2") (pinfunction "2_2") (pintype "passive"))
      (node (ref "U5") (pin "V1") (pinfunction "V1_V1") (pintype "bidirectional"))
    )
    (net (code "76") (name "WARNING_OUT") (class "Default")
      (node (ref "U1") (pin "8") (pinfunction "WARNING_8") (pintype "output"))
      (node (ref "U2") (pin "8") (pinfunction "WARNING_8") (pintype "output"))
      (node (ref "U3") (pin "10") (pinfunction "10/TX2/PWM_10") (pintype "bidirectional"))
    )
    (net (code "77") (name "unconnected-(U2-IN+3-Pad2)") (class "Default")
      (node (ref "U2") (pin "2") (pinfunction "IN+3_2") (pintype "input"))
    )
    (net (code "78") (name "unconnected-(U3-0{slash}RX1{slash}T-Pad0)") (class "Default")
      (node (ref "U3") (pin "0") (pinfunction "0/RX1/T_0") (pintype "bidirectional"))
    )
    (net (code "79") (name "unconnected-(U3-1{slash}TX1{slash}T-Pad1)") (class "Default")
      (node (ref "U3") (pin "1") (pinfunction "1/TX1/T_1") (pintype "bidirectional"))
    )
    (net (code "80") (name "unconnected-(U3-5{slash}PWM-Pad5)") (class "Default")
      (node (ref "U3") (pin "5") (pinfunction "5/PWM_5") (pintype "bidirectional"))
    )
    (net (code "81") (name "unconnected-(U3-6{slash}PWM-Pad6)") (class "Default")
      (node (ref "U3") (pin "6") (pinfunction "6/PWM_6") (pintype "bidirectional"))
    )
    (net (code "82") (name "unconnected-(U3-11{slash}MOSI-Pad11)") (class "Default")
      (node (ref "U3") (pin "11") (pinfunction "11/MOSI_11") (pintype "bidirectional"))
    )
    (net (code "83") (name "unconnected-(U3-12{slash}MISO-Pad12)") (class "Default")
      (node (ref "U3") (pin "12") (pinfunction "12/MISO_12") (pintype "bidirectional"))
    )
    (net (code "84") (name "unconnected-(U3-13{slash}SCK{slash}LED-Pad13)") (class "Default")
      (node (ref "U3") (pin "13") (pinfunction "13/SCK/LED_13") (pintype "bidirectional"))
    )
    (net (code "85") (name "unconnected-(U3-15{slash}A1{slash}T-Pad15{slash}A1)") (class "Default")
      (node (ref "U3") (pin "15/A1") (pinfunction "15/A1/T_15/A1") (pintype "bidirectional"))
    )
    (net (code "86") (name "unconnected-(U3-16{slash}A2{slash}T-Pad16{slash}A2)") (class "Default")
      (node (ref "U3") (pin "16/A2") (pinfunction "16/A2/T_16/A2") (pintype "bidirectional"))
    )
    (net (code "87") (name "unconnected-(U3-17{slash}A3{slash}T-Pad17{slash}A3)") (class "Default")
      (node (ref "U3") (pin "17/A3") (pinfunction "17/A3/T_17/A3") (pintype "bidirectional"))
    )
    (net (code "88") (name "unconnected-(U3-20{slash}A6{slash}PWM-Pad20{slash}A6)") (class "Default")
      (node (ref "U3") (pin "20/A6") (pinfunction "20/A6/PWM_20/A6") (pintype "bidirectional"))
    )
    (net (code "89") (name "unconnected-(U3-21{slash}A7{slash}PWM-Pad21{slash}A7)") (class "Default")
      (node (ref "U3") (pin "21/A7") (pinfunction "21/A7/PWM_21/A7") (pintype "bidirectional"))
    )
    (net (code "90") (name "unconnected-(U3-22{slash}A8{slash}T{slash}PWM-Pad22{slash}A8)") (class "Default")
      (node (ref "U3") (pin "22/A8") (pinfunction "22/A8/T/PWM_22/A8") (pintype "bidirectional"))
    )
    (net (code "91") (name "unconnected-(U3-23{slash}A9{slash}T{slash}PWM-Pad23{slash}A9)") (class "Default")
      (node (ref "U3") (pin "23/A9") (pinfunction "23/A9/T/PWM_23/A9") (pintype "bidirectional"))
    )
    (net (code "92") (name "unconnected-(U3-Pad2)") (class "Default")
      (node (ref "U3") (pin "2") (pinfunction "2_2") (pintype "bidirectional"))
    )
    (net (code "93") (name "unconnected-(U3-Pad14{slash}A0)") (class "Default")
      (node (ref "U3") (pin "14/A0") (pinfunction "14/A0_14/A0") (pintype "bidirectional"))
    )
    (net (code "94") (name "unconnected-(U5-PadCAS)") (class "Default")
      (node (ref "U5") (pin "CAS") (pinfunction "CAS_CAS") (pintype "bidirectional"))
    )
  )
)
